# MTRduino_Rev2_0.net
KiCad netlist of a schematic drawn in EAGLE
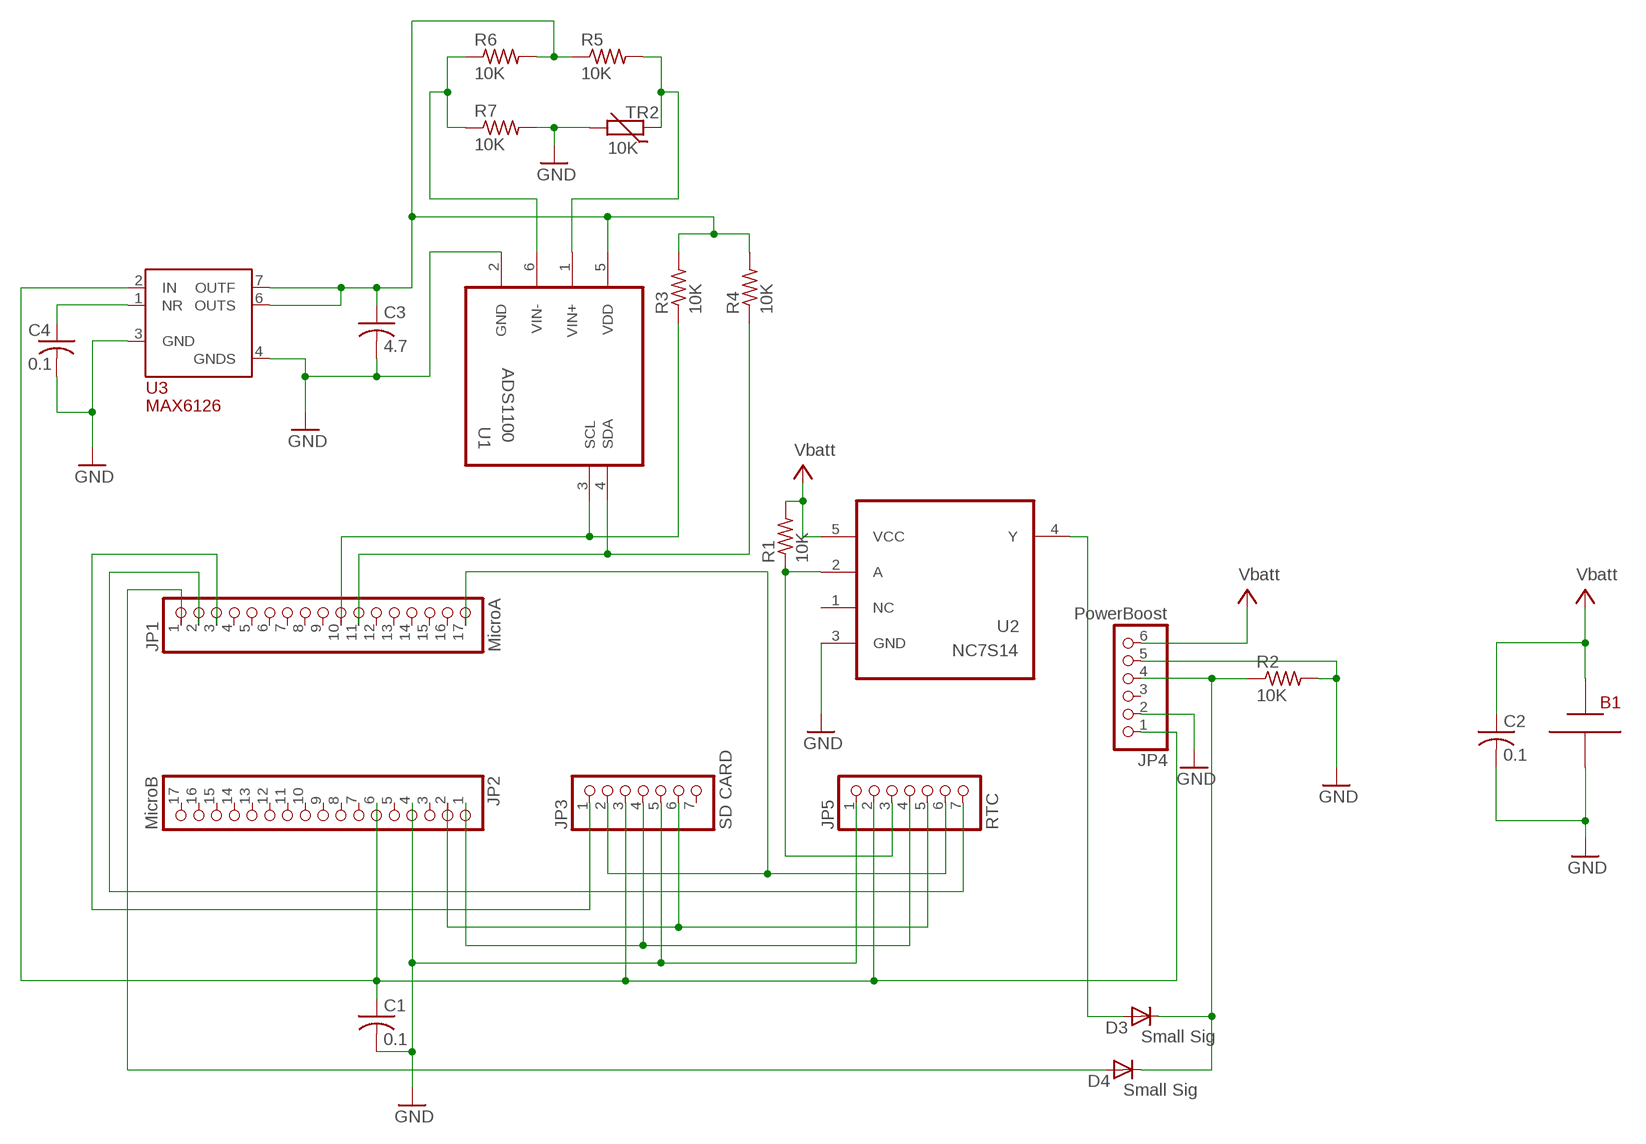
[diagram p0: schematic, sheet 1]

(export (version "E")
  (design (tool "Eeschema 10.0.6"))
  (components
    (comp (ref "B1")
      (value "2 AA BATT")
      (footprint "eagle-import:BATT_AA2")
      (libsource (lib "eagle-import") (part "BATT_AA2"))
    )
    (comp (ref "C1")
      (value "0.1")
      (footprint "eagle-import:C0603")
      (libsource (lib "eagle-import") (part "C-USC0603"))
    )
    (comp (ref "C2")
      (value "0.1")
      (footprint "eagle-import:C0603")
      (libsource (lib "eagle-import") (part "C-USC0603"))
    )
    (comp (ref "C3")
      (value "4.7")
      (footprint "eagle-import:C0603")
      (libsource (lib "eagle-import") (part "C-USC0603"))
    )
    (comp (ref "C4")
      (value "0.1")
      (footprint "eagle-import:C0603")
      (libsource (lib "eagle-import") (part "C-USC0603"))
    )
    (comp (ref "D3")
      (value "Small Sig")
      (footprint "eagle-import:SOD-323F")
      (libsource (lib "eagle-import") (part "DIODESOD-323F"))
    )
    (comp (ref "D4")
      (value "Small Sig")
      (footprint "eagle-import:SOD-323F")
      (libsource (lib "eagle-import") (part "DIODESOD-323F"))
    )
    (comp (ref "JP1")
      (value "MicroA")
      (footprint "eagle-import:1X17")
      (libsource (lib "eagle-import") (part "PINHD-1X17"))
    )
    (comp (ref "JP2")
      (value "MicroB")
      (footprint "eagle-import:1X17")
      (libsource (lib "eagle-import") (part "PINHD-1X17"))
    )
    (comp (ref "JP3")
      (value "SD CARD")
      (footprint "eagle-import:1X07")
      (libsource (lib "eagle-import") (part "PINHD-1X7"))
    )
    (comp (ref "JP4")
      (value "PowerBoost")
      (footprint "eagle-import:1X06")
      (libsource (lib "eagle-import") (part "PINHD-1X6"))
    )
    (comp (ref "JP5")
      (value "RTC")
      (footprint "eagle-import:1X07")
      (libsource (lib "eagle-import") (part "PINHD-1X7"))
    )
    (comp (ref "R1")
      (value "10K")
      (footprint "eagle-import:R0603")
      (libsource (lib "eagle-import") (part "R-US_R0603"))
    )
    (comp (ref "R2")
      (value "10K")
      (footprint "eagle-import:R0603")
      (libsource (lib "eagle-import") (part "R-US_R0603"))
    )
    (comp (ref "R3")
      (value "10K")
      (footprint "eagle-import:R0603")
      (libsource (lib "eagle-import") (part "R-US_R0603"))
    )
    (comp (ref "R4")
      (value "10K")
      (footprint "eagle-import:R0603")
      (libsource (lib "eagle-import") (part "R-US_R0603"))
    )
    (comp (ref "R5")
      (value "10K")
      (footprint "eagle-import:R0603")
      (libsource (lib "eagle-import") (part "R-US_R0603"))
    )
    (comp (ref "R6")
      (value "10K")
      (footprint "eagle-import:R0603")
      (libsource (lib "eagle-import") (part "R-US_R0603"))
    )
    (comp (ref "R7")
      (value "10K")
      (footprint "eagle-import:R0603")
      (libsource (lib "eagle-import") (part "R-US_R0603"))
    )
    (comp (ref "TR2")
      (value "10K")
      (footprint "eagle-import:R-5")
      (libsource (lib "eagle-import") (part "THERMISTOR_R-5"))
    )
    (comp (ref "U1")
      (value "ADS1100")
      (footprint "eagle-import:SOT95P280X145-6N")
      (fields (field (name "MPN") "ADS1100A0IDBVT"))
      (libsource (lib "eagle-import") (part "ADS1100A0IDBVT"))
    )
    (comp (ref "U2")
      (value "NC7S14")
      (footprint "eagle-import:SOT95P280X145-5N")
      (fields (field (name "MPN") "1P1G14MDBVREPG4"))
      (libsource (lib "eagle-import") (part "1P1G14MDBVREPG4"))
    )
    (comp (ref "U3")
      (value "MAX6126")
      (footprint "eagle-import:SOIC127P600X175-8N")
      (libsource (lib "eagle-import") (part "MAX6126"))
    )
  )
  (nets
    (net (code "1") (name "GND") (class "Default")
      (node (ref "B1") (pin "-") (pinfunction "-_-") (pintype "bidirectional"))
      (node (ref "C1") (pin "2") (pinfunction "2_2") (pintype "passive"))
      (node (ref "C2") (pin "2") (pinfunction "2_2") (pintype "passive"))
      (node (ref "C3") (pin "2") (pinfunction "2_2") (pintype "passive"))
      (node (ref "C4") (pin "2") (pinfunction "2_2") (pintype "passive"))
      (node (ref "JP2") (pin "4") (pinfunction "4_4") (pintype "passive"))
      (node (ref "JP3") (pin "5") (pinfunction "5_5") (pintype "passive"))
      (node (ref "JP4") (pin "2") (pinfunction "2_2") (pintype "passive"))
      (node (ref "JP4") (pin "5") (pinfunction "5_5") (pintype "passive"))
      (node (ref "JP5") (pin "1") (pinfunction "1_1") (pintype "passive"))
      (node (ref "R2") (pin "2") (pinfunction "2_2") (pintype "passive"))
      (node (ref "R7") (pin "2") (pinfunction "2_2") (pintype "passive"))
      (node (ref "TR2") (pin "2") (pinfunction "2_2") (pintype "passive"))
      (node (ref "U1") (pin "2") (pinfunction "GND_2") (pintype "passive"))
      (node (ref "U2") (pin "3") (pinfunction "GND_3") (pintype "passive"))
      (node (ref "U3") (pin "3") (pinfunction "GND_3") (pintype "input"))
      (node (ref "U3") (pin "4") (pinfunction "GNDS_4") (pintype "input"))
    )
    (net (code "2") (name "Net-(D3-PadC)") (class "Default")
      (node (ref "D3") (pin "C") (pinfunction "C_C") (pintype "passive"))
      (node (ref "D4") (pin "C") (pinfunction "C_C") (pintype "passive"))
      (node (ref "JP4") (pin "4") (pinfunction "4_4") (pintype "passive"))
      (node (ref "R2") (pin "1") (pinfunction "1_1") (pintype "passive"))
    )
    (net (code "3") (name "Net-(D4-PadA)") (class "Default")
      (node (ref "D4") (pin "A") (pinfunction "A_A") (pintype "passive"))
      (node (ref "JP1") (pin "1") (pinfunction "1_1") (pintype "passive"))
    )
    (net (code "4") (name "Net-(JP1-Pad2)") (class "Default")
      (node (ref "JP1") (pin "2") (pinfunction "2_2") (pintype "passive"))
      (node (ref "JP5") (pin "7") (pinfunction "7_7") (pintype "passive"))
    )
    (net (code "5") (name "Net-(JP1-Pad3)") (class "Default")
      (node (ref "JP1") (pin "3") (pinfunction "3_3") (pintype "passive"))
      (node (ref "JP3") (pin "1") (pinfunction "1_1") (pintype "passive"))
    )
    (net (code "6") (name "Net-(JP1-Pad17)") (class "Default")
      (node (ref "JP1") (pin "17") (pinfunction "17_17") (pintype "passive"))
      (node (ref "JP3") (pin "2") (pinfunction "2_2") (pintype "passive"))
      (node (ref "JP5") (pin "6") (pinfunction "6_6") (pintype "passive"))
    )
    (net (code "7") (name "Net-(JP2-Pad1)") (class "Default")
      (node (ref "JP2") (pin "1") (pinfunction "1_1") (pintype "passive"))
      (node (ref "JP3") (pin "4") (pinfunction "4_4") (pintype "passive"))
      (node (ref "JP5") (pin "4") (pinfunction "4_4") (pintype "passive"))
    )
    (net (code "8") (name "Net-(JP2-Pad2)") (class "Default")
      (node (ref "JP2") (pin "2") (pinfunction "2_2") (pintype "passive"))
      (node (ref "JP3") (pin "6") (pinfunction "6_6") (pintype "passive"))
      (node (ref "JP5") (pin "5") (pinfunction "5_5") (pintype "passive"))
    )
    (net (code "9") (name "Net-(U1-SCL)") (class "Default")
      (node (ref "JP1") (pin "10") (pinfunction "10_10") (pintype "passive"))
      (node (ref "R3") (pin "1") (pinfunction "1_1") (pintype "passive"))
      (node (ref "U1") (pin "3") (pinfunction "SCL_3") (pintype "output"))
    )
    (net (code "10") (name "Net-(U1-SDA)") (class "Default")
      (node (ref "JP1") (pin "11") (pinfunction "11_11") (pintype "passive"))
      (node (ref "R4") (pin "1") (pinfunction "1_1") (pintype "passive"))
      (node (ref "U1") (pin "4") (pinfunction "SDA_4") (pintype "output"))
    )
    (net (code "11") (name "Net-(U1-VDD)") (class "Default")
      (node (ref "C3") (pin "1") (pinfunction "1_1") (pintype "passive"))
      (node (ref "R3") (pin "2") (pinfunction "2_2") (pintype "passive"))
      (node (ref "R4") (pin "2") (pinfunction "2_2") (pintype "passive"))
      (node (ref "R5") (pin "1") (pinfunction "1_1") (pintype "passive"))
      (node (ref "R6") (pin "2") (pinfunction "2_2") (pintype "passive"))
      (node (ref "U1") (pin "5") (pinfunction "VDD_5") (pintype "power_in"))
      (node (ref "U3") (pin "6") (pinfunction "OUTS_6") (pintype "output"))
      (node (ref "U3") (pin "7") (pinfunction "OUTF_7") (pintype "output"))
    )
    (net (code "12") (name "Net-(U1-VIN+)") (class "Default")
      (node (ref "R5") (pin "2") (pinfunction "2_2") (pintype "passive"))
      (node (ref "TR2") (pin "1") (pinfunction "1_1") (pintype "passive"))
      (node (ref "U1") (pin "1") (pinfunction "VIN+_1") (pintype "input"))
    )
    (net (code "13") (name "Net-(U1-VIN-)") (class "Default")
      (node (ref "R6") (pin "1") (pinfunction "1_1") (pintype "passive"))
      (node (ref "R7") (pin "1") (pinfunction "1_1") (pintype "passive"))
      (node (ref "U1") (pin "6") (pinfunction "VIN-_6") (pintype "input"))
    )
    (net (code "14") (name "Net-(U2-A)") (class "Default")
      (node (ref "JP5") (pin "3") (pinfunction "3_3") (pintype "passive"))
      (node (ref "R1") (pin "1") (pinfunction "1_1") (pintype "passive"))
      (node (ref "U2") (pin "2") (pinfunction "A_2") (pintype "input"))
    )
    (net (code "15") (name "Net-(U2-Y)") (class "Default")
      (node (ref "D3") (pin "A") (pinfunction "A_A") (pintype "passive"))
      (node (ref "U2") (pin "4") (pinfunction "Y_4") (pintype "output"))
    )
    (net (code "16") (name "Net-(U3-IN)") (class "Default")
      (node (ref "C1") (pin "1") (pinfunction "1_1") (pintype "passive"))
      (node (ref "JP2") (pin "6") (pinfunction "6_6") (pintype "passive"))
      (node (ref "JP3") (pin "3") (pinfunction "3_3") (pintype "passive"))
      (node (ref "JP4") (pin "1") (pinfunction "1_1") (pintype "passive"))
      (node (ref "JP5") (pin "2") (pinfunction "2_2") (pintype "passive"))
      (node (ref "U3") (pin "2") (pinfunction "IN_2") (pintype "input"))
    )
    (net (code "17") (name "Net-(U3-NR)") (class "Default")
      (node (ref "C4") (pin "1") (pinfunction "1_1") (pintype "passive"))
      (node (ref "U3") (pin "1") (pinfunction "NR_1") (pintype "bidirectional"))
    )
    (net (code "18") (name "Vbatt") (class "Default")
      (node (ref "B1") (pin "+") (pinfunction "+_+") (pintype "bidirectional"))
      (node (ref "C2") (pin "1") (pinfunction "1_1") (pintype "passive"))
      (node (ref "JP4") (pin "6") (pinfunction "6_6") (pintype "passive"))
      (node (ref "R1") (pin "2") (pinfunction "2_2") (pintype "passive"))
      (node (ref "U2") (pin "5") (pinfunction "VCC_5") (pintype "power_in"))
    )
    (net (code "19") (name "unconnected-(JP1-Pad4)") (class "Default")
      (node (ref "JP1") (pin "4") (pinfunction "4_4") (pintype "passive"))
    )
    (net (code "20") (name "unconnected-(JP1-Pad5)") (class "Default")
      (node (ref "JP1") (pin "5") (pinfunction "5_5") (pintype "passive"))
    )
    (net (code "21") (name "unconnected-(JP1-Pad6)") (class "Default")
      (node (ref "JP1") (pin "6") (pinfunction "6_6") (pintype "passive"))
    )
    (net (code "22") (name "unconnected-(JP1-Pad7)") (class "Default")
      (node (ref "JP1") (pin "7") (pinfunction "7_7") (pintype "passive"))
    )
    (net (code "23") (name "unconnected-(JP1-Pad8)") (class "Default")
      (node (ref "JP1") (pin "8") (pinfunction "8_8") (pintype "passive"))
    )
    (net (code "24") (name "unconnected-(JP1-Pad9)") (class "Default")
      (node (ref "JP1") (pin "9") (pinfunction "9_9") (pintype "passive"))
    )
    (net (code "25") (name "unconnected-(JP1-Pad12)") (class "Default")
      (node (ref "JP1") (pin "12") (pinfunction "12_12") (pintype "passive"))
    )
    (net (code "26") (name "unconnected-(JP1-Pad13)") (class "Default")
      (node (ref "JP1") (pin "13") (pinfunction "13_13") (pintype "passive"))
    )
    (net (code "27") (name "unconnected-(JP1-Pad14)") (class "Default")
      (node (ref "JP1") (pin "14") (pinfunction "14_14") (pintype "passive"))
    )
    (net (code "28") (name "unconnected-(JP1-Pad15)") (class "Default")
      (node (ref "JP1") (pin "15") (pinfunction "15_15") (pintype "passive"))
    )
    (net (code "29") (name "unconnected-(JP1-Pad16)") (class "Default")
      (node (ref "JP1") (pin "16") (pinfunction "16_16") (pintype "passive"))
    )
    (net (code "30") (name "unconnected-(JP2-Pad3)") (class "Default")
      (node (ref "JP2") (pin "3") (pinfunction "3_3") (pintype "passive"))
    )
    (net (code "31") (name "unconnected-(JP2-Pad5)") (class "Default")
      (node (ref "JP2") (pin "5") (pinfunction "5_5") (pintype "passive"))
    )
    (net (code "32") (name "unconnected-(JP2-Pad7)") (class "Default")
      (node (ref "JP2") (pin "7") (pinfunction "7_7") (pintype "passive"))
    )
    (net (code "33") (name "unconnected-(JP2-Pad8)") (class "Default")
      (node (ref "JP2") (pin "8") (pinfunction "8_8") (pintype "passive"))
    )
    (net (code "34") (name "unconnected-(JP2-Pad9)") (class "Default")
      (node (ref "JP2") (pin "9") (pinfunction "9_9") (pintype "passive"))
    )
    (net (code "35") (name "unconnected-(JP2-Pad10)") (class "Default")
      (node (ref "JP2") (pin "10") (pinfunction "10_10") (pintype "passive"))
    )
    (net (code "36") (name "unconnected-(JP2-Pad11)") (class "Default")
      (node (ref "JP2") (pin "11") (pinfunction "11_11") (pintype "passive"))
    )
    (net (code "37") (name "unconnected-(JP2-Pad12)") (class "Default")
      (node (ref "JP2") (pin "12") (pinfunction "12_12") (pintype "passive"))
    )
    (net (code "38") (name "unconnected-(JP2-Pad13)") (class "Default")
      (node (ref "JP2") (pin "13") (pinfunction "13_13") (pintype "passive"))
    )
    (net (code "39") (name "unconnected-(JP2-Pad14)") (class "Default")
      (node (ref "JP2") (pin "14") (pinfunction "14_14") (pintype "passive"))
    )
    (net (code "40") (name "unconnected-(JP2-Pad15)") (class "Default")
      (node (ref "JP2") (pin "15") (pinfunction "15_15") (pintype "passive"))
    )
    (net (code "41") (name "unconnected-(JP2-Pad16)") (class "Default")
      (node (ref "JP2") (pin "16") (pinfunction "16_16") (pintype "passive"))
    )
    (net (code "42") (name "unconnected-(JP2-Pad17)") (class "Default")
      (node (ref "JP2") (pin "17") (pinfunction "17_17") (pintype "passive"))
    )
    (net (code "43") (name "unconnected-(JP3-Pad7)") (class "Default")
      (node (ref "JP3") (pin "7") (pinfunction "7_7") (pintype "passive"))
    )
    (net (code "44") (name "unconnected-(JP4-Pad3)") (class "Default")
      (node (ref "JP4") (pin "3") (pinfunction "3_3") (pintype "passive"))
    )
    (net (code "45") (name "unconnected-(U2-NC-Pad1)") (class "Default")
      (node (ref "U2") (pin "1") (pinfunction "NC_1") (pintype "no_connect"))
    )
  )
)
